# USB_to_UART.net
KiCad netlist of a schematic drawn in Altium Designer
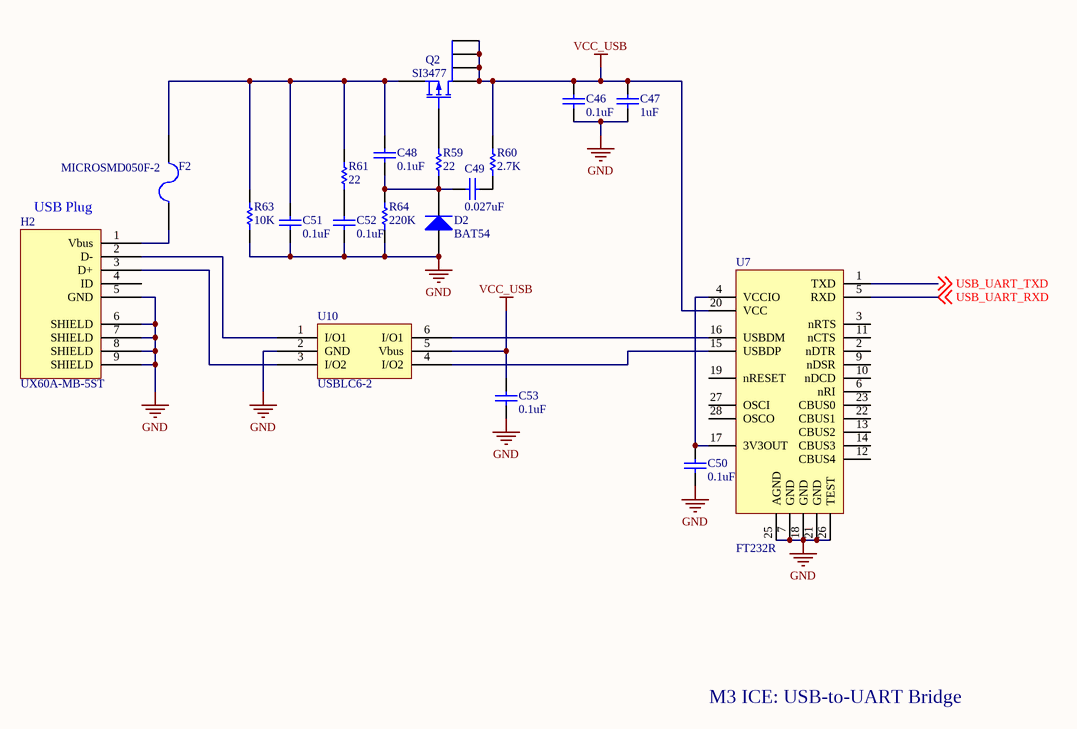
[diagram p0: USB_to_UART.SchDoc]

(export (version "E")
  (design (tool "Eeschema 10.0.6"))
  (components
    (comp (ref "C46")
      (value "0.1uF")
      (footprint "1608[0603]")
      (description "Capacitor (Semiconductor SIM Model)")
      (fields
        (field (name "DISTPARTNO") "445-1317-1-ND")
        (field (name "MANPARTNO") "C1608X7R1C104K")
        (field (name "PUBLISHER") "Altium Limited")
      )
      (libsource (lib "Miscellaneous Devices") (part "Cap Semi"))
    )
    (comp (ref "C47")
      (value "1uF")
      (footprint "1608[0603]")
      (description "Capacitor (Semiconductor SIM Model)")
      (fields
        (field (name "DISTPARTNO") "445-1327-1-ND")
        (field (name "MANPARTNO") "C1608Y5V1C105Z")
        (field (name "PUBLISHER") "Altium Limited")
      )
      (libsource (lib "Miscellaneous Devices") (part "Cap Semi"))
    )
    (comp (ref "C48")
      (value "0.1uF")
      (footprint "1608[0603]")
      (description "Capacitor (Semiconductor SIM Model)")
      (fields
        (field (name "DISTPARTNO") "445-1317-1-ND")
        (field (name "MANPARTNO") "C1608X7R1C104K")
        (field (name "PUBLISHER") "Altium Limited")
      )
      (libsource (lib "Miscellaneous Devices") (part "Cap Semi"))
    )
    (comp (ref "C49")
      (value "0.027uF")
      (footprint "1608[0603]")
      (description "Capacitor (Semiconductor SIM Model)")
      (fields
        (field (name "DISTPARTNO") "478-1232-1-ND")
        (field (name "MANPARTNO") "06035C273KAT2A")
        (field (name "PUBLISHER") "Altium Limited")
      )
      (libsource (lib "Miscellaneous Devices") (part "Cap Semi"))
    )
    (comp (ref "C50")
      (value "0.1uF")
      (footprint "1608[0603]")
      (description "Capacitor (Semiconductor SIM Model)")
      (fields
        (field (name "DISTPARTNO") "445-1317-1-ND")
        (field (name "MANPARTNO") "C1608X7R1C104K")
        (field (name "PUBLISHER") "Altium Limited")
      )
      (libsource (lib "Miscellaneous Devices") (part "Cap Semi"))
    )
    (comp (ref "C51")
      (value "0.1uF")
      (footprint "1608[0603]")
      (description "Capacitor (Semiconductor SIM Model)")
      (fields
        (field (name "DISTPARTNO") "445-1317-1-ND")
        (field (name "MANPARTNO") "C1608X7R1C104K")
        (field (name "PUBLISHER") "Altium Limited")
      )
      (libsource (lib "Miscellaneous Devices") (part "Cap Semi"))
    )
    (comp (ref "C52")
      (value "0.1uF")
      (footprint "1608[0603]")
      (description "Capacitor (Semiconductor SIM Model)")
      (fields
        (field (name "DISTPARTNO") "445-1317-1-ND")
        (field (name "MANPARTNO") "C1608X7R1C104K")
        (field (name "PUBLISHER") "Altium Limited")
      )
      (libsource (lib "Miscellaneous Devices") (part "Cap Semi"))
    )
    (comp (ref "C53")
      (value "0.1uF")
      (footprint "1608[0603]")
      (description "Capacitor (Semiconductor SIM Model)")
      (fields
        (field (name "DISTPARTNO") "445-1317-1-ND")
        (field (name "MANPARTNO") "C1608X7R1C104K")
        (field (name "PUBLISHER") "Altium Limited")
      )
      (libsource (lib "Miscellaneous Devices") (part "Cap Semi"))
    )
    (comp (ref "D2")
      (value "BAT54")
      (footprint "SOT-23_N")
      (description "Low-Loss RF Switching Diode")
      (fields
        (field (name "DISTPARTNO") "BAT54-FDICT-ND")
        (field (name "MANPARTNO") "BAT54-7-F")
        (field (name "PUBLISHER") "Altium Limited")
      )
      (libsource (lib "Miscellaneous Devices") (part "Diode BAT18"))
    )
    (comp (ref "F2")
      (value "MICROSMD050F-2")
      (footprint "1210")
      (description "POLYSWITCH 0.50A RESET FUSE SMD")
      (fields (field (name "DISTPARTNO") "MICROSMD050FCT-ND"))
      (libsource (lib "M3") (part "Fuse MICROSMD050F-2"))
    )
    (comp (ref "H2")
      (value "UX60A-MB-5ST")
      (footprint "USB Mini-B")
      (description "USB mini-B")
      (fields (field (name "DISTPARTNO") "H2961CT-ND"))
      (libsource (lib "M3") (part "UX60-MB-5ST"))
    )
    (comp (ref "Q2")
      (value "SI3477")
      (footprint "TSOP-6")
      (description "P-Channel MOSFET")
      (fields (field (name "DISTPARTNO") "SI3477DV-T1-GE3CT-ND") (field (name "MANPARTNO") "SI3477DV-T1-GE3"))
      (libsource (lib "M3") (part "SI3477"))
    )
    (comp (ref "R59")
      (value "22")
      (footprint "0603")
      (description "Semiconductor Resistor")
      (fields
        (field (name "DISTPARTNO") "P22GCT-ND")
        (field (name "MANPARTNO") "ERJ-3GEYJ220V")
        (field (name "PUBLISHER") "Altium Limited")
      )
      (libsource (lib "M3") (part "Res Chip"))
    )
    (comp (ref "R60")
      (value "2.7K")
      (footprint "0603")
      (description "Semiconductor Resistor")
      (fields
        (field (name "DISTPARTNO") "P2.7KGCT-ND")
        (field (name "MANPARTNO") "ERJ-3GEYJ272V")
        (field (name "PUBLISHER") "Altium Limited")
      )
      (libsource (lib "M3") (part "Res Chip"))
    )
    (comp (ref "R61")
      (value "22")
      (footprint "0603")
      (description "Semiconductor Resistor")
      (fields
        (field (name "DISTPARTNO") "P22GCT-ND")
        (field (name "MANPARTNO") "ERJ-3GEYJ220V")
        (field (name "PUBLISHER") "Altium Limited")
      )
      (libsource (lib "M3") (part "Res Chip"))
    )
    (comp (ref "R63")
      (value "10K")
      (footprint "0603")
      (description "Semiconductor Resistor")
      (fields
        (field (name "DISTPARTNO") "P10KGCT-ND")
        (field (name "MANPARTNO") "ERJ-3GEYJ103V")
        (field (name "PUBLISHER") "Altium Limited")
      )
      (libsource (lib "M3") (part "Res Chip"))
    )
    (comp (ref "R64")
      (value "220K")
      (footprint "0603")
      (description "Semiconductor Resistor")
      (fields
        (field (name "DISTPARTNO") "P220KGCT-ND")
        (field (name "MANPARTNO") "ERJ-3GEYJ224V")
        (field (name "PUBLISHER") "Altium Limited")
      )
      (libsource (lib "M3") (part "Res Chip"))
    )
    (comp (ref "U7")
      (value "FT232R")
      (footprint "SSOP20")
      (fields (field (name "DISTPARTNO") "768-1007-1-ND") (field (name "MANPARTNO") "FT232RL-REEL"))
      (libsource (lib "uwb-library") (part "FT232R"))
    )
    (comp (ref "U10")
      (value "USBLC6-2")
      (footprint "SOT23-6_L")
      (description "USB ESD Protection")
      (fields (field (name "DISTPARTNO") "497-11882-1-ND") (field (name "MANPARTNO") "USBLC6-2SC6Y"))
      (libsource (lib "M3") (part "USBLC6-2"))
    )
  )
  (nets
    (net (code "1") (name "GND") (class "Default")
      (node (ref "C46") (pin "1") (pinfunction "1_1") (pintype "passive"))
      (node (ref "C47") (pin "1") (pinfunction "1_1") (pintype "passive"))
      (node (ref "C50") (pin "1") (pinfunction "1_1") (pintype "passive"))
      (node (ref "C51") (pin "1") (pinfunction "1_1") (pintype "passive"))
      (node (ref "C52") (pin "1") (pinfunction "1_1") (pintype "passive"))
      (node (ref "C53") (pin "1") (pinfunction "1_1") (pintype "passive"))
      (node (ref "D2") (pin "1") (pinfunction "A_1") (pintype "passive"))
      (node (ref "H2") (pin "5") (pinfunction "GND_5") (pintype "passive"))
      (node (ref "H2") (pin "6") (pinfunction "SHIELD_6") (pintype "passive"))
      (node (ref "H2") (pin "7") (pinfunction "SHIELD_7") (pintype "passive"))
      (node (ref "H2") (pin "8") (pinfunction "SHIELD_8") (pintype "passive"))
      (node (ref "H2") (pin "9") (pinfunction "SHIELD_9") (pintype "passive"))
      (node (ref "R63") (pin "1") (pinfunction "1_1") (pintype "passive"))
      (node (ref "R64") (pin "1") (pinfunction "1_1") (pintype "passive"))
      (node (ref "U10") (pin "2") (pinfunction "GND_2") (pintype "passive"))
      (node (ref "U7") (pin "18") (pinfunction "GND_18") (pintype "passive"))
      (node (ref "U7") (pin "21") (pinfunction "GND_21") (pintype "passive"))
      (node (ref "U7") (pin "25") (pinfunction "AGND_25") (pintype "passive"))
      (node (ref "U7") (pin "26") (pinfunction "TEST_26") (pintype "passive"))
      (node (ref "U7") (pin "7") (pinfunction "GND_7") (pintype "passive"))
    )
    (net (code "2") (name "Net-(C49-Pad1)") (class "Default")
      (node (ref "C49") (pin "1") (pinfunction "1_1") (pintype "passive"))
      (node (ref "R60") (pin "1") (pinfunction "1_1") (pintype "passive"))
    )
    (net (code "3") (name "Net-(C52-Pad2)") (class "Default")
      (node (ref "C52") (pin "2") (pinfunction "2_2") (pintype "passive"))
      (node (ref "R61") (pin "1") (pinfunction "1_1") (pintype "passive"))
    )
    (net (code "4") (name "Net-(D2-K)") (class "Default")
      (node (ref "C48") (pin "1") (pinfunction "1_1") (pintype "passive"))
      (node (ref "C49") (pin "2") (pinfunction "2_2") (pintype "passive"))
      (node (ref "D2") (pin "3") (pinfunction "K_3") (pintype "passive"))
      (node (ref "R59") (pin "1") (pinfunction "1_1") (pintype "passive"))
      (node (ref "R64") (pin "2") (pinfunction "2_2") (pintype "passive"))
    )
    (net (code "5") (name "Net-(H2-D+)") (class "Default")
      (node (ref "H2") (pin "3") (pinfunction "D+_3") (pintype "passive"))
      (node (ref "U10") (pin "3") (pinfunction "I/O2_3") (pintype "passive"))
    )
    (net (code "6") (name "Net-(H2-D-)") (class "Default")
      (node (ref "H2") (pin "2") (pinfunction "D-_2") (pintype "passive"))
      (node (ref "U10") (pin "1") (pinfunction "I/O1_1") (pintype "passive"))
    )
    (net (code "7") (name "Net-(H2-Vbus)") (class "Default")
      (node (ref "F2") (pin "1") (pinfunction "1_1") (pintype "passive"))
      (node (ref "H2") (pin "1") (pinfunction "Vbus_1") (pintype "passive"))
    )
    (net (code "8") (name "Net-(Q2-G)") (class "Default")
      (node (ref "Q2") (pin "3") (pinfunction "G_3") (pintype "passive"))
      (node (ref "R59") (pin "2") (pinfunction "2_2") (pintype "passive"))
    )
    (net (code "9") (name "Net-(Q2-S)") (class "Default")
      (node (ref "C48") (pin "2") (pinfunction "2_2") (pintype "passive"))
      (node (ref "C51") (pin "2") (pinfunction "2_2") (pintype "passive"))
      (node (ref "F2") (pin "2") (pinfunction "2_2") (pintype "passive"))
      (node (ref "Q2") (pin "4") (pinfunction "S_4") (pintype "passive"))
      (node (ref "R61") (pin "2") (pinfunction "2_2") (pintype "passive"))
      (node (ref "R63") (pin "2") (pinfunction "2_2") (pintype "passive"))
    )
    (net (code "10") (name "Net-(U7-3V3OUT)") (class "Default")
      (node (ref "C50") (pin "2") (pinfunction "2_2") (pintype "passive"))
      (node (ref "U7") (pin "17") (pinfunction "3V3OUT_17") (pintype "passive"))
      (node (ref "U7") (pin "4") (pinfunction "VCCIO_4") (pintype "passive"))
    )
    (net (code "11") (name "Net-(U7-USBDM)") (class "Default")
      (node (ref "U10") (pin "6") (pinfunction "I/O1_6") (pintype "passive"))
      (node (ref "U7") (pin "16") (pinfunction "USBDM_16") (pintype "passive"))
    )
    (net (code "12") (name "Net-(U7-USBDP)") (class "Default")
      (node (ref "U10") (pin "4") (pinfunction "I/O2_4") (pintype "passive"))
      (node (ref "U7") (pin "15") (pinfunction "USBDP_15") (pintype "passive"))
    )
    (net (code "13") (name "USB_UART_RXD") (class "Default")
      (node (ref "U7") (pin "5") (pinfunction "RXD_5") (pintype "passive"))
    )
    (net (code "14") (name "USB_UART_TXD") (class "Default")
      (node (ref "U7") (pin "1") (pinfunction "TXD_1") (pintype "passive"))
    )
    (net (code "15") (name "VCC_USB") (class "Default")
      (node (ref "C46") (pin "2") (pinfunction "2_2") (pintype "passive"))
      (node (ref "C47") (pin "2") (pinfunction "2_2") (pintype "passive"))
      (node (ref "C53") (pin "2") (pinfunction "2_2") (pintype "passive"))
      (node (ref "Q2") (pin "1") (pinfunction "D_1") (pintype "passive"))
      (node (ref "Q2") (pin "2") (pinfunction "D_2") (pintype "passive"))
      (node (ref "Q2") (pin "5") (pinfunction "D_5") (pintype "passive"))
      (node (ref "Q2") (pin "6") (pinfunction "D_6") (pintype "passive"))
      (node (ref "R60") (pin "2") (pinfunction "2_2") (pintype "passive"))
      (node (ref "U10") (pin "5") (pinfunction "Vbus_5") (pintype "passive"))
      (node (ref "U7") (pin "20") (pinfunction "VCC_20") (pintype "passive"))
    )
    (net (code "16") (name "unconnected-(H2-ID-Pad4)") (class "Default")
      (node (ref "H2") (pin "4") (pinfunction "ID_4") (pintype "passive"))
    )
    (net (code "17") (name "unconnected-(U7-CBUS0-Pad23)") (class "Default")
      (node (ref "U7") (pin "23") (pinfunction "CBUS0_23") (pintype "passive"))
    )
    (net (code "18") (name "unconnected-(U7-CBUS1-Pad22)") (class "Default")
      (node (ref "U7") (pin "22") (pinfunction "CBUS1_22") (pintype "passive"))
    )
    (net (code "19") (name "unconnected-(U7-CBUS2-Pad13)") (class "Default")
      (node (ref "U7") (pin "13") (pinfunction "CBUS2_13") (pintype "passive"))
    )
    (net (code "20") (name "unconnected-(U7-CBUS3-Pad14)") (class "Default")
      (node (ref "U7") (pin "14") (pinfunction "CBUS3_14") (pintype "passive"))
    )
    (net (code "21") (name "unconnected-(U7-CBUS4-Pad12)") (class "Default")
      (node (ref "U7") (pin "12") (pinfunction "CBUS4_12") (pintype "passive"))
    )
    (net (code "22") (name "unconnected-(U7-OSCI-Pad27)") (class "Default")
      (node (ref "U7") (pin "27") (pinfunction "OSCI_27") (pintype "passive"))
    )
    (net (code "23") (name "unconnected-(U7-OSCO-Pad28)") (class "Default")
      (node (ref "U7") (pin "28") (pinfunction "OSCO_28") (pintype "passive"))
    )
    (net (code "24") (name "unconnected-(U7-nCTS-Pad11)") (class "Default")
      (node (ref "U7") (pin "11") (pinfunction "nCTS_11") (pintype "passive"))
    )
    (net (code "25") (name "unconnected-(U7-nDCD-Pad10)") (class "Default")
      (node (ref "U7") (pin "10") (pinfunction "nDCD_10") (pintype "passive"))
    )
    (net (code "26") (name "unconnected-(U7-nDSR-Pad9)") (class "Default")
      (node (ref "U7") (pin "9") (pinfunction "nDSR_9") (pintype "passive"))
    )
    (net (code "27") (name "unconnected-(U7-nDTR-Pad2)") (class "Default")
      (node (ref "U7") (pin "2") (pinfunction "nDTR_2") (pintype "passive"))
    )
    (net (code "28") (name "unconnected-(U7-nRESET-Pad19)") (class "Default")
      (node (ref "U7") (pin "19") (pinfunction "nRESET_19") (pintype "passive"))
    )
    (net (code "29") (name "unconnected-(U7-nRI-Pad6)") (class "Default")
      (node (ref "U7") (pin "6") (pinfunction "nRI_6") (pintype "passive"))
    )
    (net (code "30") (name "unconnected-(U7-nRTS-Pad3)") (class "Default")
      (node (ref "U7") (pin "3") (pinfunction "nRTS_3") (pintype "passive"))
    )
  )
)
